# STM32F100C_GB_Controller.net
KiCad netlist of a schematic drawn in EAGLE
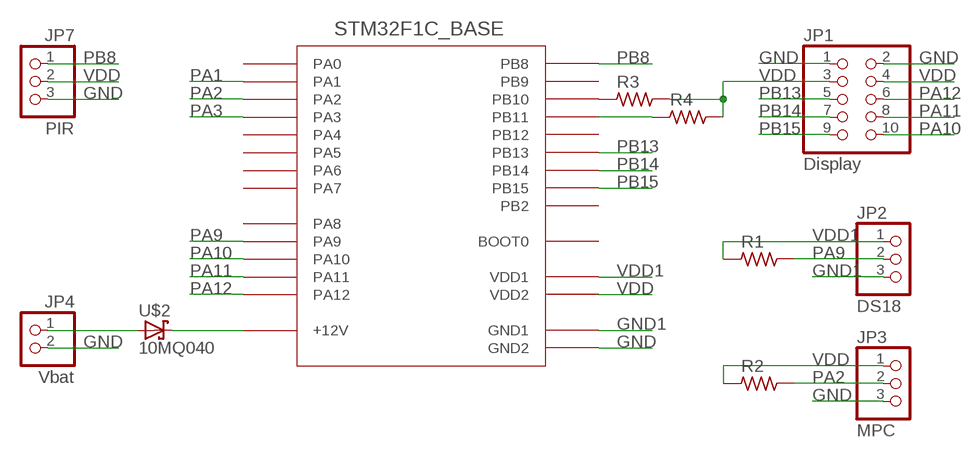
[diagram p0: schematic, sheet 1]

(export (version "E")
  (design (tool "Eeschema 10.0.6"))
  (components
    (comp (ref "JP1")
      (value "Display")
      (footprint "eagle-import:2X05")
      (libsource (lib "eagle-import") (part "PINHD-2X05_2.54"))
    )
    (comp (ref "JP2")
      (value "DS18")
      (footprint "eagle-import:1X03-S")
      (libsource (lib "eagle-import") (part "PINHD-1X03_2.54-S"))
    )
    (comp (ref "JP3")
      (value "MPC")
      (footprint "eagle-import:1X03-S")
      (libsource (lib "eagle-import") (part "PINHD-1X03_2.54-S"))
    )
    (comp (ref "JP4")
      (value "Vbat")
      (footprint "eagle-import:1X02-S")
      (libsource (lib "eagle-import") (part "PINHD-1X02_2.54-S"))
    )
    (comp (ref "JP7")
      (value "PIR")
      (footprint "eagle-import:1X03-S")
      (libsource (lib "eagle-import") (part "PINHD-1X03_2.54-S"))
    )
    (comp (ref "R1")
      (value "R_1206")
      (footprint "eagle-import:R1206")
      (libsource (lib "eagle-import") (part "R_1206"))
    )
    (comp (ref "R2")
      (value "R_1206")
      (footprint "eagle-import:R1206")
      (libsource (lib "eagle-import") (part "R_1206"))
    )
    (comp (ref "R3")
      (value "R_1206")
      (footprint "eagle-import:R1206")
      (libsource (lib "eagle-import") (part "R_1206"))
    )
    (comp (ref "R4")
      (value "R_1206")
      (footprint "eagle-import:R1206")
      (libsource (lib "eagle-import") (part "R_1206"))
    )
    (comp (ref "U$1")
      (value "STM32F1C_BASE")
      (footprint "eagle-import:STM32F1_BASE")
      (libsource (lib "eagle-import") (part "STM32F1C_BASE"))
    )
    (comp (ref "U$2")
      (value "10MQ040")
      (footprint "eagle-import:SMA")
      (libsource (lib "eagle-import") (part "10MQ040"))
    )
  )
  (nets
    (net (code "1") (name "/GND") (class "Default")
      (node (ref "JP1") (pin "1") (pinfunction "1_1") (pintype "passive"))
      (node (ref "JP1") (pin "2") (pinfunction "2_2") (pintype "passive"))
      (node (ref "JP3") (pin "3") (pinfunction "3_3") (pintype "passive"))
      (node (ref "JP4") (pin "2") (pinfunction "2_2") (pintype "passive"))
      (node (ref "JP7") (pin "3") (pinfunction "3_3") (pintype "passive"))
      (node (ref "U$1") (pin "GND1") (pinfunction "GND2_GND1") (pintype "power_in"))
    )
    (net (code "2") (name "/GND1") (class "Default")
      (node (ref "JP2") (pin "3") (pinfunction "3_3") (pintype "passive"))
      (node (ref "U$1") (pin "GND") (pinfunction "GND1_GND") (pintype "power_in"))
    )
    (net (code "3") (name "/PA1") (class "Default")
      (node (ref "U$1") (pin "PA1") (pinfunction "PA1_PA1") (pintype "passive"))
    )
    (net (code "4") (name "/PA2") (class "Default")
      (node (ref "JP3") (pin "2") (pinfunction "2_2") (pintype "passive"))
      (node (ref "R2") (pin "2") (pinfunction "2_2") (pintype "passive"))
      (node (ref "U$1") (pin "PA2") (pinfunction "PA2_PA2") (pintype "passive"))
    )
    (net (code "5") (name "/PA3") (class "Default")
      (node (ref "U$1") (pin "PA3") (pinfunction "PA3_PA3") (pintype "passive"))
    )
    (net (code "6") (name "/PA9") (class "Default")
      (node (ref "JP2") (pin "2") (pinfunction "2_2") (pintype "passive"))
      (node (ref "R1") (pin "2") (pinfunction "2_2") (pintype "passive"))
      (node (ref "U$1") (pin "PA9") (pinfunction "PA9_PA9") (pintype "passive"))
    )
    (net (code "7") (name "/PA10") (class "Default")
      (node (ref "JP1") (pin "10") (pinfunction "10_10") (pintype "passive"))
      (node (ref "U$1") (pin "PA10") (pinfunction "PA10_PA10") (pintype "passive"))
    )
    (net (code "8") (name "/PA11") (class "Default")
      (node (ref "JP1") (pin "8") (pinfunction "8_8") (pintype "passive"))
      (node (ref "U$1") (pin "PA11") (pinfunction "PA11_PA11") (pintype "passive"))
    )
    (net (code "9") (name "/PA12") (class "Default")
      (node (ref "JP1") (pin "6") (pinfunction "6_6") (pintype "passive"))
      (node (ref "U$1") (pin "PA12") (pinfunction "PA12_PA12") (pintype "passive"))
    )
    (net (code "10") (name "/PB8") (class "Default")
      (node (ref "JP7") (pin "1") (pinfunction "1_1") (pintype "passive"))
      (node (ref "U$1") (pin "PB8") (pinfunction "PB8_PB8") (pintype "passive"))
    )
    (net (code "11") (name "/PB13") (class "Default")
      (node (ref "JP1") (pin "5") (pinfunction "5_5") (pintype "passive"))
      (node (ref "U$1") (pin "PB13") (pinfunction "PB13_PB13") (pintype "passive"))
    )
    (net (code "12") (name "/PB14") (class "Default")
      (node (ref "JP1") (pin "7") (pinfunction "7_7") (pintype "passive"))
      (node (ref "U$1") (pin "PB14") (pinfunction "PB14_PB14") (pintype "passive"))
    )
    (net (code "13") (name "/PB15") (class "Default")
      (node (ref "JP1") (pin "9") (pinfunction "9_9") (pintype "passive"))
      (node (ref "U$1") (pin "PB15") (pinfunction "PB15_PB15") (pintype "passive"))
    )
    (net (code "14") (name "/VDD") (class "Default")
      (node (ref "JP1") (pin "3") (pinfunction "3_3") (pintype "passive"))
      (node (ref "JP1") (pin "4") (pinfunction "4_4") (pintype "passive"))
      (node (ref "JP3") (pin "1") (pinfunction "1_1") (pintype "passive"))
      (node (ref "JP7") (pin "2") (pinfunction "2_2") (pintype "passive"))
      (node (ref "R2") (pin "1") (pinfunction "1_1") (pintype "passive"))
      (node (ref "R3") (pin "2") (pinfunction "2_2") (pintype "passive"))
      (node (ref "R4") (pin "2") (pinfunction "2_2") (pintype "passive"))
      (node (ref "U$1") (pin "3.3_1") (pinfunction "VDD2_3.3_1") (pintype "power_in"))
    )
    (net (code "15") (name "/VDD1") (class "Default")
      (node (ref "JP2") (pin "1") (pinfunction "1_1") (pintype "passive"))
      (node (ref "R1") (pin "1") (pinfunction "1_1") (pintype "passive"))
      (node (ref "U$1") (pin "3.3") (pinfunction "VDD1_3.3") (pintype "power_in"))
    )
    (net (code "16") (name "Net-(JP4-Pad1)") (class "Default")
      (node (ref "JP4") (pin "1") (pinfunction "1_1") (pintype "passive"))
      (node (ref "U$2") (pin "A") (pinfunction "A_A") (pintype "passive"))
    )
    (net (code "17") (name "Net-(R3-Pad1)") (class "Default")
      (node (ref "R3") (pin "1") (pinfunction "1_1") (pintype "passive"))
      (node (ref "U$1") (pin "PB10") (pinfunction "PB10_PB10") (pintype "passive"))
    )
    (net (code "18") (name "Net-(R4-Pad1)") (class "Default")
      (node (ref "R4") (pin "1") (pinfunction "1_1") (pintype "passive"))
      (node (ref "U$1") (pin "PB11") (pinfunction "PB11_PB11") (pintype "passive"))
    )
    (net (code "19") (name "Net-(U$1-+12V)") (class "Default")
      (node (ref "U$1") (pin "+12") (pinfunction "+12V_+12") (pintype "power_in"))
      (node (ref "U$2") (pin "C") (pinfunction "C_C") (pintype "passive"))
    )
    (net (code "20") (name "unconnected-(U$1-PB2-PadB2)") (class "Default")
      (node (ref "U$1") (pin "B2") (pinfunction "PB2_B2") (pintype "passive"))
    )
    (net (code "21") (name "unconnected-(U$1-PadBOOT0)") (class "Default")
      (node (ref "U$1") (pin "BOOT0") (pinfunction "BOOT0_BOOT0") (pintype "passive"))
    )
    (net (code "22") (name "unconnected-(U$1-PadPA0)") (class "Default")
      (node (ref "U$1") (pin "PA0") (pinfunction "PA0_PA0") (pintype "passive"))
    )
    (net (code "23") (name "unconnected-(U$1-PadPA4)") (class "Default")
      (node (ref "U$1") (pin "PA4") (pinfunction "PA4_PA4") (pintype "passive"))
    )
    (net (code "24") (name "unconnected-(U$1-PadPA5)") (class "Default")
      (node (ref "U$1") (pin "PA5") (pinfunction "PA5_PA5") (pintype "passive"))
    )
    (net (code "25") (name "unconnected-(U$1-PadPA6)") (class "Default")
      (node (ref "U$1") (pin "PA6") (pinfunction "PA6_PA6") (pintype "passive"))
    )
    (net (code "26") (name "unconnected-(U$1-PadPA7)") (class "Default")
      (node (ref "U$1") (pin "PA7") (pinfunction "PA7_PA7") (pintype "passive"))
    )
    (net (code "27") (name "unconnected-(U$1-PadPA8)") (class "Default")
      (node (ref "U$1") (pin "PA8") (pinfunction "PA8_PA8") (pintype "passive"))
    )
    (net (code "28") (name "unconnected-(U$1-PadPB9)") (class "Default")
      (node (ref "U$1") (pin "PB9") (pinfunction "PB9_PB9") (pintype "passive"))
    )
    (net (code "29") (name "unconnected-(U$1-PadPB12)") (class "Default")
      (node (ref "U$1") (pin "PB12") (pinfunction "PB12_PB12") (pintype "passive"))
    )
  )
)
